# STM32L476VE.net
KiCad netlist of a schematic drawn in Altium Designer
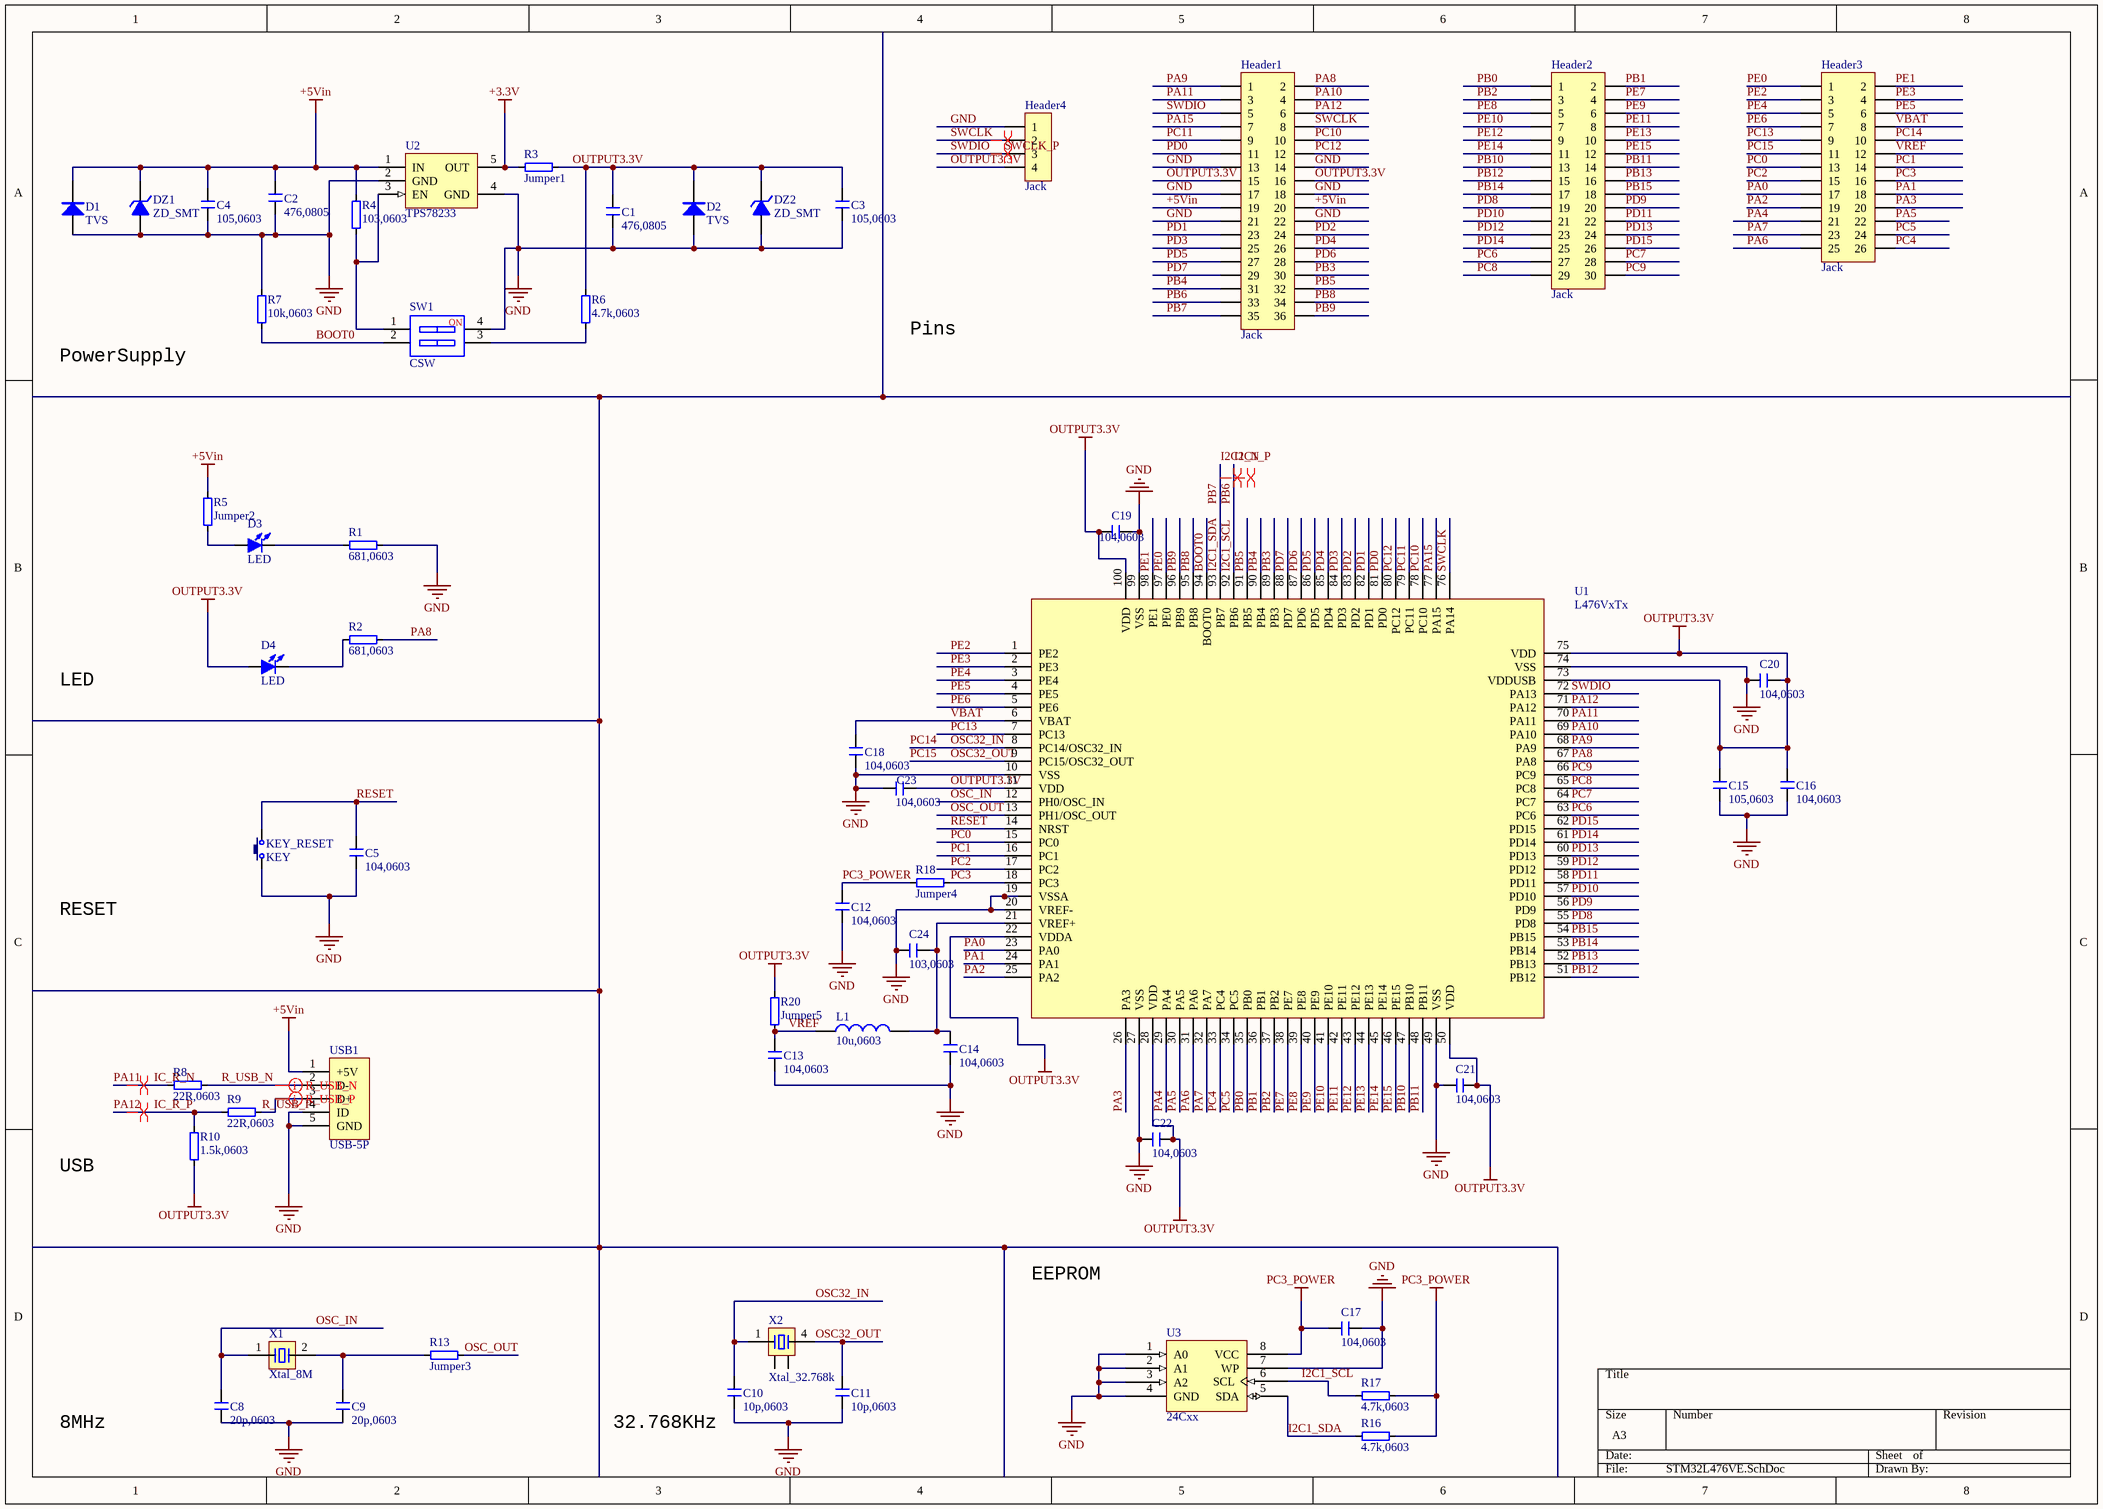
[diagram p0: STM32L476VE.SchDoc]

(export (version "E")
  (design (tool "Eeschema 10.0.6"))
  (components
    (comp (ref "C1")
      (value "476,0805")
      (footprint "0805C")
      (description "SMT0805")
      (libsource (lib "STM32L476VE") (part "CC_SMT_1"))
    )
    (comp (ref "C2")
      (value "476,0805")
      (footprint "0805C")
      (description "SMT0805")
      (libsource (lib "STM32L476VE") (part "CC_SMT_1"))
    )
    (comp (ref "C3")
      (value "105,0603")
      (footprint "0603_R")
      (description "SMT0603")
      (libsource (lib "STM32L476VE") (part "CC_SMT"))
    )
    (comp (ref "C4")
      (value "105,0603")
      (footprint "0603_R")
      (description "SMT0603")
      (libsource (lib "STM32L476VE") (part "CC_SMT"))
    )
    (comp (ref "C5")
      (value "104,0603")
      (footprint "0603_R")
      (description "SMT0603")
      (libsource (lib "STM32L476VE") (part "CC_SMT"))
    )
    (comp (ref "C8")
      (value "20p,0603")
      (footprint "0603_R")
      (description "SMT0603")
      (libsource (lib "STM32L476VE") (part "CC_SMT"))
    )
    (comp (ref "C9")
      (value "20p,0603")
      (footprint "0603_R")
      (description "SMT0603")
      (libsource (lib "STM32L476VE") (part "CC_SMT"))
    )
    (comp (ref "C10")
      (value "10p,0603")
      (footprint "0603_R")
      (description "SMT0603")
      (libsource (lib "STM32L476VE") (part "CC_SMT"))
    )
    (comp (ref "C11")
      (value "10p,0603")
      (footprint "0603_R")
      (description "SMT0603")
      (libsource (lib "STM32L476VE") (part "CC_SMT"))
    )
    (comp (ref "C12")
      (value "104,0603")
      (footprint "0603_R")
      (description "SMT0603")
      (libsource (lib "STM32L476VE") (part "CC_SMT"))
    )
    (comp (ref "C13")
      (value "104,0603")
      (footprint "0603_R")
      (description "SMT0603")
      (libsource (lib "STM32L476VE") (part "CC_SMT"))
    )
    (comp (ref "C14")
      (value "104,0603")
      (footprint "0603_R")
      (description "SMT0603")
      (libsource (lib "STM32L476VE") (part "CC_SMT"))
    )
    (comp (ref "C15")
      (value "105,0603")
      (footprint "0603_R")
      (description "SMT0603")
      (libsource (lib "STM32L476VE") (part "CC_SMT"))
    )
    (comp (ref "C16")
      (value "104,0603")
      (footprint "0603_R")
      (description "SMT0603")
      (libsource (lib "STM32L476VE") (part "CC_SMT"))
    )
    (comp (ref "C17")
      (value "104,0603")
      (footprint "0603_R")
      (description "SMT0603")
      (libsource (lib "STM32L476VE") (part "CC_SMT"))
    )
    (comp (ref "C18")
      (value "104,0603")
      (footprint "0603_R")
      (description "SMT0603")
      (libsource (lib "STM32L476VE") (part "CC_SMT"))
    )
    (comp (ref "C19")
      (value "104,0603")
      (footprint "0603_R")
      (description "SMT0603")
      (libsource (lib "STM32L476VE") (part "CC_SMT"))
    )
    (comp (ref "C20")
      (value "104,0603")
      (footprint "0603_R")
      (description "SMT0603")
      (libsource (lib "STM32L476VE") (part "CC_SMT"))
    )
    (comp (ref "C21")
      (value "104,0603")
      (footprint "0603_R")
      (description "SMT0603")
      (libsource (lib "STM32L476VE") (part "CC_SMT"))
    )
    (comp (ref "C22")
      (value "104,0603")
      (footprint "0603_R")
      (description "SMT0603")
      (libsource (lib "STM32L476VE") (part "CC_SMT"))
    )
    (comp (ref "C23")
      (value "104,0603")
      (footprint "0603_R")
      (description "SMT0603")
      (libsource (lib "STM32L476VE") (part "CC_SMT"))
    )
    (comp (ref "C24")
      (value "103,0603")
      (footprint "0603_R")
      (description "SMT0603")
      (libsource (lib "STM32L476VE") (part "CC_SMT"))
    )
    (comp (ref "D1")
      (value "TVS")
      (footprint "SMB(DO-214AA)_S3")
      (description "TVS Diode")
      (fields (field (name "版权归属") "源创客"))
      (libsource (lib "STM32L476VE") (part "TVS_SMT"))
    )
    (comp (ref "D2")
      (value "TVS")
      (footprint "SMB(DO-214AA)_S3")
      (description "TVS Diode")
      (fields (field (name "版权归属") "源创客"))
      (libsource (lib "STM32L476VE") (part "TVS_SMT"))
    )
    (comp (ref "D3")
      (value "LED")
      (footprint "LED0603")
      (description "LED_0603")
      (libsource (lib "STM32L476VE") (part "LED0603"))
    )
    (comp (ref "D4")
      (value "LED")
      (footprint "LED0603")
      (description "LED_0603")
      (libsource (lib "STM32L476VE") (part "LED0603"))
    )
    (comp (ref "DZ1")
      (value "ZD_SMT")
      (footprint "MINI_MELF (LL34)")
      (description "Zener")
      (libsource (lib "STM32L476VE") (part "ZD_SMT"))
    )
    (comp (ref "DZ2")
      (value "ZD_SMT")
      (footprint "MINI_MELF (LL34)")
      (description "Zener")
      (libsource (lib "STM32L476VE") (part "ZD_SMT"))
    )
    (comp (ref "Header1")
      (value "Jack")
      (footprint "HDR2.54-LI-2x18P")
      (description "Header Male")
      (libsource (lib "STM32L476VE") (part "M_18X2Pins_2.54-DIP"))
    )
    (comp (ref "Header2")
      (value "Jack")
      (footprint "HDR2.54-LI-2x15P")
      (description "Header Male")
      (libsource (lib "STM32L476VE") (part "M_15X2Pins_2.54-DIP"))
    )
    (comp (ref "Header3")
      (value "Jack")
      (footprint "HDR2.54-LI-2x13P")
      (description "Header Male")
      (libsource (lib "STM32L476VE") (part "M_13X2Pins_2.54-DIP"))
    )
    (comp (ref "Header4")
      (value "Jack")
      (footprint "HDR2.54-LI-4P")
      (description "Header Male")
      (libsource (lib "STM32L476VE") (part "M_4Pins_2.54-DIP"))
    )
    (comp (ref "KEY_RESET")
      (value "KEY")
      (footprint "TSW SMD-4*4*1.5")
      (description "Tact Switch")
      (libsource (lib "STM32L476VE") (part "TSW_4x4-SMT"))
    )
    (comp (ref "L1")
      (value "10u,0603")
      (footprint "L 0603")
      (description "SMT_0603")
      (libsource (lib "STM32L476VE") (part "L_SMT"))
    )
    (comp (ref "R1")
      (value "681,0603")
      (footprint "0603_R")
      (description "SMT_0603")
      (libsource (lib "STM32L476VE") (part "R_SMT"))
    )
    (comp (ref "R2")
      (value "681,0603")
      (footprint "0603_R")
      (description "SMT_0603")
      (libsource (lib "STM32L476VE") (part "R_SMT"))
    )
    (comp (ref "R3")
      (value "Jumper1")
      (footprint "0805C")
      (description "SMT_0805")
      (libsource (lib "STM32L476VE") (part "R_SMT_1"))
    )
    (comp (ref "R4")
      (value "103,0603")
      (footprint "0603_R")
      (description "SMT_0603")
      (libsource (lib "STM32L476VE") (part "R_SMT"))
    )
    (comp (ref "R5")
      (value "Jumper2")
      (footprint "0603_R")
      (description "SMT_0603")
      (libsource (lib "STM32L476VE") (part "R_SMT"))
    )
    (comp (ref "R6")
      (value "4.7k,0603")
      (footprint "0603_R")
      (description "SMT_0603")
      (libsource (lib "STM32L476VE") (part "R_SMT"))
    )
    (comp (ref "R7")
      (value "10k,0603")
      (footprint "0603_R")
      (description "SMT_0603")
      (libsource (lib "STM32L476VE") (part "R_SMT"))
    )
    (comp (ref "R8")
      (value "22R,0603")
      (footprint "0603_R")
      (description "SMT_0603")
      (libsource (lib "STM32L476VE") (part "R_SMT"))
    )
    (comp (ref "R9")
      (value "22R,0603")
      (footprint "0603_R")
      (description "SMT_0603")
      (libsource (lib "STM32L476VE") (part "R_SMT"))
    )
    (comp (ref "R10")
      (value "1.5k,0603")
      (footprint "0603_R")
      (description "SMT_0603")
      (libsource (lib "STM32L476VE") (part "R_SMT"))
    )
    (comp (ref "R13")
      (value "Jumper3")
      (footprint "0603_R")
      (description "SMT_0603")
      (libsource (lib "STM32L476VE") (part "R_SMT"))
    )
    (comp (ref "R16")
      (value "4.7k,0603")
      (footprint "0603_R")
      (description "SMT_0603")
      (libsource (lib "STM32L476VE") (part "R_SMT"))
    )
    (comp (ref "R17")
      (value "4.7k,0603")
      (footprint "0603_R")
      (description "SMT_0603")
      (libsource (lib "STM32L476VE") (part "R_SMT"))
    )
    (comp (ref "R18")
      (value "Jumper4")
      (footprint "0603_R")
      (description "SMT_0603")
      (libsource (lib "STM32L476VE") (part "R_SMT"))
    )
    (comp (ref "R20")
      (value "Jumper5")
      (footprint "0603_R")
      (description "SMT_0603")
      (libsource (lib "STM32L476VE") (part "R_SMT"))
    )
    (comp (ref "SW1")
      (value "CSW")
      (footprint "CSW1.27 SMD-2P")
      (description "DialSwitch")
      (libsource (lib "STM32L476VE") (part "Switch2_SMT"))
    )
    (comp (ref "U1")
      (value "L476VxTx")
      (footprint "LQFP-100_14x14x05P")
      (libsource (lib "STM32L476VE") (part "STM32L476VxTx"))
    )
    (comp (ref "U2")
      (value "TPS78233")
      (footprint "SOT23-5L")
      (description "Regulator_SMT")
      (fields (field (name "版权归属") "源创客"))
      (libsource (lib "STM32L476VE") (part "TPS782"))
    )
    (comp (ref "U3")
      (value "24Cxx")
      (footprint "SOIC-8_150mil")
      (description "外置EEPROM")
      (fields (field (name "版权归属") "源创客"))
      (libsource (lib "STM32L476VE") (part "24Cxx"))
    )
    (comp (ref "USB1")
      (value "USB-5P")
      (footprint "USB-MICRO_E")
      (description "USB_SMT")
      (fields (field (name "版权归属") "源创客"))
      (libsource (lib "STM32L476VE") (part "USB-5P"))
    )
    (comp (ref "X1")
      (value "Xtal_8M")
      (footprint "SMD-5032_2P")
      (fields (field (name "版权归属") "源创客"))
      (libsource (lib "STM32L476VE") (part "XTAL_8M_SMT"))
    )
    (comp (ref "X2")
      (value "Xtal_32.768k")
      (footprint "OSC MC-306")
      (fields (field (name "版权归属") "源创客"))
      (libsource (lib "STM32L476VE") (part "XTAL_32.768K_SMT"))
    )
  )
  (nets
    (net (code "1") (name "+3.3V") (class "Default")
      (node (ref "R3") (pin "1") (pinfunction "1_1") (pintype "passive"))
      (node (ref "U2") (pin "5") (pinfunction "OUT_5") (pintype "passive"))
    )
    (net (code "2") (name "+5Vin") (class "Default")
      (node (ref "C2") (pin "1") (pinfunction "1_1") (pintype "passive"))
      (node (ref "C4") (pin "1") (pinfunction "1_1") (pintype "passive"))
      (node (ref "D1") (pin "2") (pinfunction "K_2") (pintype "passive"))
      (node (ref "DZ1") (pin "2") (pinfunction "K_2") (pintype "passive"))
      (node (ref "Header1") (pin "19") (pinfunction "19_19") (pintype "passive"))
      (node (ref "Header1") (pin "20") (pinfunction "20_20") (pintype "passive"))
      (node (ref "R4") (pin "2") (pinfunction "2_2") (pintype "passive"))
      (node (ref "R5") (pin "2") (pinfunction "2_2") (pintype "passive"))
      (node (ref "U2") (pin "1") (pinfunction "IN_1") (pintype "passive"))
      (node (ref "USB1") (pin "1") (pinfunction "+5V_1") (pintype "passive"))
    )
    (net (code "3") (name "/BOOT0") (class "Default")
      (node (ref "R7") (pin "2") (pinfunction "2_2") (pintype "passive"))
      (node (ref "SW1") (pin "2") (pinfunction "2_2") (pintype "passive"))
      (node (ref "U1") (pin "94") (pinfunction "BOOT0_94") (pintype "passive"))
    )
    (net (code "4") (name "/I2C1_N") (class "Default")
      (node (ref "Header1") (pin "35") (pinfunction "35_35") (pintype "passive"))
      (node (ref "R16") (pin "1") (pinfunction "1_1") (pintype "passive"))
      (node (ref "U1") (pin "93") (pinfunction "PB7_93") (pintype "passive"))
      (node (ref "U3") (pin "5") (pinfunction "SDA_5") (pintype "bidirectional"))
    )
    (net (code "5") (name "/I2C1_P") (class "Default")
      (node (ref "Header1") (pin "33") (pinfunction "33_33") (pintype "passive"))
      (node (ref "R17") (pin "1") (pinfunction "1_1") (pintype "passive"))
      (node (ref "U1") (pin "92") (pinfunction "PB6_92") (pintype "passive"))
      (node (ref "U3") (pin "6") (pinfunction "SCL_6") (pintype "input"))
    )
    (net (code "6") (name "/IC_R_N") (class "Default")
      (node (ref "Header1") (pin "3") (pinfunction "3_3") (pintype "passive"))
      (node (ref "R8") (pin "1") (pinfunction "1_1") (pintype "passive"))
      (node (ref "U1") (pin "70") (pinfunction "PA11_70") (pintype "passive"))
    )
    (net (code "7") (name "/IC_R_P") (class "Default")
      (node (ref "Header1") (pin "6") (pinfunction "6_6") (pintype "passive"))
      (node (ref "R10") (pin "2") (pinfunction "2_2") (pintype "passive"))
      (node (ref "R9") (pin "1") (pinfunction "1_1") (pintype "passive"))
      (node (ref "U1") (pin "71") (pinfunction "PA12_71") (pintype "passive"))
    )
    (net (code "8") (name "/OSC32_IN") (class "Default")
      (node (ref "C10") (pin "1") (pinfunction "1_1") (pintype "passive"))
      (node (ref "Header3") (pin "10") (pinfunction "10_10") (pintype "passive"))
      (node (ref "U1") (pin "8") (pinfunction "PC14/OSC32_IN_8") (pintype "passive"))
      (node (ref "X2") (pin "1") (pinfunction "1_1") (pintype "passive"))
    )
    (net (code "9") (name "/OSC32_OUT") (class "Default")
      (node (ref "C11") (pin "1") (pinfunction "1_1") (pintype "passive"))
      (node (ref "Header3") (pin "11") (pinfunction "11_11") (pintype "passive"))
      (node (ref "U1") (pin "9") (pinfunction "PC15/OSC32_OUT_9") (pintype "passive"))
      (node (ref "X2") (pin "4") (pinfunction "4_4") (pintype "passive"))
    )
    (net (code "10") (name "/OSC_IN") (class "Default")
      (node (ref "C8") (pin "1") (pinfunction "1_1") (pintype "passive"))
      (node (ref "U1") (pin "12") (pinfunction "PH0/OSC_IN_12") (pintype "passive"))
      (node (ref "X1") (pin "1") (pinfunction "1_1") (pintype "passive"))
    )
    (net (code "11") (name "/OSC_OUT") (class "Default")
      (node (ref "R13") (pin "2") (pinfunction "2_2") (pintype "passive"))
      (node (ref "U1") (pin "13") (pinfunction "PH1/OSC_OUT_13") (pintype "passive"))
    )
    (net (code "12") (name "/PA0") (class "Default")
      (node (ref "Header3") (pin "17") (pinfunction "17_17") (pintype "passive"))
      (node (ref "U1") (pin "23") (pinfunction "PA0_23") (pintype "passive"))
    )
    (net (code "13") (name "/PA1") (class "Default")
      (node (ref "Header3") (pin "18") (pinfunction "18_18") (pintype "passive"))
      (node (ref "U1") (pin "24") (pinfunction "PA1_24") (pintype "passive"))
    )
    (net (code "14") (name "/PA2") (class "Default")
      (node (ref "Header3") (pin "19") (pinfunction "19_19") (pintype "passive"))
      (node (ref "U1") (pin "25") (pinfunction "PA2_25") (pintype "passive"))
    )
    (net (code "15") (name "/PA3") (class "Default")
      (node (ref "Header3") (pin "20") (pinfunction "20_20") (pintype "passive"))
      (node (ref "U1") (pin "26") (pinfunction "PA3_26") (pintype "passive"))
    )
    (net (code "16") (name "/PA4") (class "Default")
      (node (ref "Header3") (pin "21") (pinfunction "21_21") (pintype "passive"))
      (node (ref "U1") (pin "29") (pinfunction "PA4_29") (pintype "passive"))
    )
    (net (code "17") (name "/PA5") (class "Default")
      (node (ref "Header3") (pin "22") (pinfunction "22_22") (pintype "passive"))
      (node (ref "U1") (pin "30") (pinfunction "PA5_30") (pintype "passive"))
    )
    (net (code "18") (name "/PA6") (class "Default")
      (node (ref "Header3") (pin "25") (pinfunction "25_25") (pintype "passive"))
      (node (ref "U1") (pin "31") (pinfunction "PA6_31") (pintype "passive"))
    )
    (net (code "19") (name "/PA7") (class "Default")
      (node (ref "Header3") (pin "23") (pinfunction "23_23") (pintype "passive"))
      (node (ref "U1") (pin "32") (pinfunction "PA7_32") (pintype "passive"))
    )
    (net (code "20") (name "/PA8") (class "Default")
      (node (ref "Header1") (pin "2") (pinfunction "2_2") (pintype "passive"))
      (node (ref "R2") (pin "2") (pinfunction "2_2") (pintype "passive"))
      (node (ref "U1") (pin "67") (pinfunction "PA8_67") (pintype "passive"))
    )
    (net (code "21") (name "/PA9") (class "Default")
      (node (ref "Header1") (pin "1") (pinfunction "1_1") (pintype "passive"))
      (node (ref "U1") (pin "68") (pinfunction "PA9_68") (pintype "passive"))
    )
    (net (code "22") (name "/PA10") (class "Default")
      (node (ref "Header1") (pin "4") (pinfunction "4_4") (pintype "passive"))
      (node (ref "U1") (pin "69") (pinfunction "PA10_69") (pintype "passive"))
    )
    (net (code "23") (name "/PA15") (class "Default")
      (node (ref "Header1") (pin "7") (pinfunction "7_7") (pintype "passive"))
      (node (ref "U1") (pin "77") (pinfunction "PA15_77") (pintype "passive"))
    )
    (net (code "24") (name "/PB0") (class "Default")
      (node (ref "Header2") (pin "1") (pinfunction "1_1") (pintype "passive"))
      (node (ref "U1") (pin "35") (pinfunction "PB0_35") (pintype "passive"))
    )
    (net (code "25") (name "/PB1") (class "Default")
      (node (ref "Header2") (pin "2") (pinfunction "2_2") (pintype "passive"))
      (node (ref "U1") (pin "36") (pinfunction "PB1_36") (pintype "passive"))
    )
    (net (code "26") (name "/PB2") (class "Default")
      (node (ref "Header2") (pin "3") (pinfunction "3_3") (pintype "passive"))
      (node (ref "U1") (pin "37") (pinfunction "PB2_37") (pintype "passive"))
    )
    (net (code "27") (name "/PB3") (class "Default")
      (node (ref "Header1") (pin "30") (pinfunction "30_30") (pintype "passive"))
      (node (ref "U1") (pin "89") (pinfunction "PB3_89") (pintype "passive"))
    )
    (net (code "28") (name "/PB4") (class "Default")
      (node (ref "Header1") (pin "31") (pinfunction "31_31") (pintype "passive"))
      (node (ref "U1") (pin "90") (pinfunction "PB4_90") (pintype "passive"))
    )
    (net (code "29") (name "/PB5") (class "Default")
      (node (ref "Header1") (pin "32") (pinfunction "32_32") (pintype "passive"))
      (node (ref "U1") (pin "91") (pinfunction "PB5_91") (pintype "passive"))
    )
    (net (code "30") (name "/PB8") (class "Default")
      (node (ref "Header1") (pin "34") (pinfunction "34_34") (pintype "passive"))
      (node (ref "U1") (pin "95") (pinfunction "PB8_95") (pintype "passive"))
    )
    (net (code "31") (name "/PB9") (class "Default")
      (node (ref "Header1") (pin "36") (pinfunction "36_36") (pintype "passive"))
      (node (ref "U1") (pin "96") (pinfunction "PB9_96") (pintype "passive"))
    )
    (net (code "32") (name "/PB10") (class "Default")
      (node (ref "Header2") (pin "13") (pinfunction "13_13") (pintype "passive"))
      (node (ref "U1") (pin "47") (pinfunction "PB10_47") (pintype "passive"))
    )
    (net (code "33") (name "/PB11") (class "Default")
      (node (ref "Header2") (pin "14") (pinfunction "14_14") (pintype "passive"))
      (node (ref "U1") (pin "48") (pinfunction "PB11_48") (pintype "passive"))
    )
    (net (code "34") (name "/PB12") (class "Default")
      (node (ref "Header2") (pin "15") (pinfunction "15_15") (pintype "passive"))
      (node (ref "U1") (pin "51") (pinfunction "PB12_51") (pintype "passive"))
    )
    (net (code "35") (name "/PB13") (class "Default")
      (node (ref "Header2") (pin "16") (pinfunction "16_16") (pintype "passive"))
      (node (ref "U1") (pin "52") (pinfunction "PB13_52") (pintype "passive"))
    )
    (net (code "36") (name "/PB14") (class "Default")
      (node (ref "Header2") (pin "17") (pinfunction "17_17") (pintype "passive"))
      (node (ref "U1") (pin "53") (pinfunction "PB14_53") (pintype "passive"))
    )
    (net (code "37") (name "/PB15") (class "Default")
      (node (ref "Header2") (pin "18") (pinfunction "18_18") (pintype "passive"))
      (node (ref "U1") (pin "54") (pinfunction "PB15_54") (pintype "passive"))
    )
    (net (code "38") (name "/PC0") (class "Default")
      (node (ref "Header3") (pin "13") (pinfunction "13_13") (pintype "passive"))
      (node (ref "U1") (pin "15") (pinfunction "PC0_15") (pintype "passive"))
    )
    (net (code "39") (name "/PC1") (class "Default")
      (node (ref "Header3") (pin "14") (pinfunction "14_14") (pintype "passive"))
      (node (ref "U1") (pin "16") (pinfunction "PC1_16") (pintype "passive"))
    )
    (net (code "40") (name "/PC2") (class "Default")
      (node (ref "Header3") (pin "15") (pinfunction "15_15") (pintype "passive"))
      (node (ref "U1") (pin "17") (pinfunction "PC2_17") (pintype "passive"))
    )
    (net (code "41") (name "/PC3") (class "Default")
      (node (ref "Header3") (pin "16") (pinfunction "16_16") (pintype "passive"))
      (node (ref "R18") (pin "2") (pinfunction "2_2") (pintype "passive"))
      (node (ref "U1") (pin "18") (pinfunction "PC3_18") (pintype "passive"))
    )
    (net (code "42") (name "/PC4") (class "Default")
      (node (ref "Header3") (pin "26") (pinfunction "26_26") (pintype "passive"))
      (node (ref "U1") (pin "33") (pinfunction "PC4_33") (pintype "passive"))
    )
    (net (code "43") (name "/PC5") (class "Default")
      (node (ref "Header3") (pin "24") (pinfunction "24_24") (pintype "passive"))
      (node (ref "U1") (pin "34") (pinfunction "PC5_34") (pintype "passive"))
    )
    (net (code "44") (name "/PC6") (class "Default")
      (node (ref "Header2") (pin "27") (pinfunction "27_27") (pintype "passive"))
      (node (ref "U1") (pin "63") (pinfunction "PC6_63") (pintype "passive"))
    )
    (net (code "45") (name "/PC7") (class "Default")
      (node (ref "Header2") (pin "28") (pinfunction "28_28") (pintype "passive"))
      (node (ref "U1") (pin "64") (pinfunction "PC7_64") (pintype "passive"))
    )
    (net (code "46") (name "/PC8") (class "Default")
      (node (ref "Header2") (pin "29") (pinfunction "29_29") (pintype "passive"))
      (node (ref "U1") (pin "65") (pinfunction "PC8_65") (pintype "passive"))
    )
    (net (code "47") (name "/PC9") (class "Default")
      (node (ref "Header2") (pin "30") (pinfunction "30_30") (pintype "passive"))
      (node (ref "U1") (pin "66") (pinfunction "PC9_66") (pintype "passive"))
    )
    (net (code "48") (name "/PC10") (class "Default")
      (node (ref "Header1") (pin "10") (pinfunction "10_10") (pintype "passive"))
      (node (ref "U1") (pin "78") (pinfunction "PC10_78") (pintype "passive"))
    )
    (net (code "49") (name "/PC11") (class "Default")
      (node (ref "Header1") (pin "9") (pinfunction "9_9") (pintype "passive"))
      (node (ref "U1") (pin "79") (pinfunction "PC11_79") (pintype "passive"))
    )
    (net (code "50") (name "/PC12") (class "Default")
      (node (ref "Header1") (pin "12") (pinfunction "12_12") (pintype "passive"))
      (node (ref "U1") (pin "80") (pinfunction "PC12_80") (pintype "passive"))
    )
    (net (code "51") (name "/PC13") (class "Default")
      (node (ref "Header3") (pin "9") (pinfunction "9_9") (pintype "passive"))
      (node (ref "U1") (pin "7") (pinfunction "PC13_7") (pintype "passive"))
    )
    (net (code "52") (name "/PD0") (class "Default")
      (node (ref "Header1") (pin "11") (pinfunction "11_11") (pintype "passive"))
      (node (ref "U1") (pin "81") (pinfunction "PD0_81") (pintype "passive"))
    )
    (net (code "53") (name "/PD1") (class "Default")
      (node (ref "Header1") (pin "23") (pinfunction "23_23") (pintype "passive"))
      (node (ref "U1") (pin "82") (pinfunction "PD1_82") (pintype "passive"))
    )
    (net (code "54") (name "/PD2") (class "Default")
      (node (ref "Header1") (pin "24") (pinfunction "24_24") (pintype "passive"))
      (node (ref "U1") (pin "83") (pinfunction "PD2_83") (pintype "passive"))
    )
    (net (code "55") (name "/PD3") (class "Default")
      (node (ref "Header1") (pin "25") (pinfunction "25_25") (pintype "passive"))
      (node (ref "U1") (pin "84") (pinfunction "PD3_84") (pintype "passive"))
    )
    (net (code "56") (name "/PD4") (class "Default")
      (node (ref "Header1") (pin "26") (pinfunction "26_26") (pintype "passive"))
      (node (ref "U1") (pin "85") (pinfunction "PD4_85") (pintype "passive"))
    )
    (net (code "57") (name "/PD5") (class "Default")
      (node (ref "Header1") (pin "27") (pinfunction "27_27") (pintype "passive"))
      (node (ref "U1") (pin "86") (pinfunction "PD5_86") (pintype "passive"))
    )
    (net (code "58") (name "/PD6") (class "Default")
      (node (ref "Header1") (pin "28") (pinfunction "28_28") (pintype "passive"))
      (node (ref "U1") (pin "87") (pinfunction "PD6_87") (pintype "passive"))
    )
    (net (code "59") (name "/PD7") (class "Default")
      (node (ref "Header1") (pin "29") (pinfunction "29_29") (pintype "passive"))
      (node (ref "U1") (pin "88") (pinfunction "PD7_88") (pintype "passive"))
    )
    (net (code "60") (name "/PD8") (class "Default")
      (node (ref "Header2") (pin "19") (pinfunction "19_19") (pintype "passive"))
      (node (ref "U1") (pin "55") (pinfunction "PD8_55") (pintype "passive"))
    )
    (net (code "61") (name "/PD9") (class "Default")
      (node (ref "Header2") (pin "20") (pinfunction "20_20") (pintype "passive"))
      (node (ref "U1") (pin "56") (pinfunction "PD9_56") (pintype "passive"))
    )
    (net (code "62") (name "/PD10") (class "Default")
      (node (ref "Header2") (pin "21") (pinfunction "21_21") (pintype "passive"))
      (node (ref "U1") (pin "57") (pinfunction "PD10_57") (pintype "passive"))
    )
    (net (code "63") (name "/PD11") (class "Default")
      (node (ref "Header2") (pin "22") (pinfunction "22_22") (pintype "passive"))
      (node (ref "U1") (pin "58") (pinfunction "PD11_58") (pintype "passive"))
    )
    (net (code "64") (name "/PD12") (class "Default")
      (node (ref "Header2") (pin "23") (pinfunction "23_23") (pintype "passive"))
      (node (ref "U1") (pin "59") (pinfunction "PD12_59") (pintype "passive"))
    )
    (net (code "65") (name "/PD13") (class "Default")
      (node (ref "Header2") (pin "24") (pinfunction "24_24") (pintype "passive"))
      (node (ref "U1") (pin "60") (pinfunction "PD13_60") (pintype "passive"))
    )
    (net (code "66") (name "/PD14") (class "Default")
      (node (ref "Header2") (pin "25") (pinfunction "25_25") (pintype "passive"))
      (node (ref "U1") (pin "61") (pinfunction "PD14_61") (pintype "passive"))
    )
    (net (code "67") (name "/PD15") (class "Default")
      (node (ref "Header2") (pin "26") (pinfunction "26_26") (pintype "passive"))
      (node (ref "U1") (pin "62") (pinfunction "PD15_62") (pintype "passive"))
    )
    (net (code "68") (name "/PE0") (class "Default")
      (node (ref "Header3") (pin "1") (pinfunction "1_1") (pintype "passive"))
      (node (ref "U1") (pin "97") (pinfunction "PE0_97") (pintype "passive"))
    )
    (net (code "69") (name "/PE1") (class "Default")
      (node (ref "Header3") (pin "2") (pinfunction "2_2") (pintype "passive"))
      (node (ref "U1") (pin "98") (pinfunction "PE1_98") (pintype "passive"))
    )
    (net (code "70") (name "/PE2") (class "Default")
      (node (ref "Header3") (pin "3") (pinfunction "3_3") (pintype "passive"))
      (node (ref "U1") (pin "1") (pinfunction "PE2_1") (pintype "passive"))
    )
    (net (code "71") (name "/PE3") (class "Default")
      (node (ref "Header3") (pin "4") (pinfunction "4_4") (pintype "passive"))
      (node (ref "U1") (pin "2") (pinfunction "PE3_2") (pintype "passive"))
    )
    (net (code "72") (name "/PE4") (class "Default")
      (node (ref "Header3") (pin "5") (pinfunction "5_5") (pintype "passive"))
      (node (ref "U1") (pin "3") (pinfunction "PE4_3") (pintype "passive"))
    )
    (net (code "73") (name "/PE5") (class "Default")
      (node (ref "Header3") (pin "6") (pinfunction "6_6") (pintype "passive"))
      (node (ref "U1") (pin "4") (pinfunction "PE5_4") (pintype "passive"))
    )
    (net (code "74") (name "/PE6") (class "Default")
      (node (ref "Header3") (pin "7") (pinfunction "7_7") (pintype "passive"))
      (node (ref "U1") (pin "5") (pinfunction "PE6_5") (pintype "passive"))
    )
    (net (code "75") (name "/PE7") (class "Default")
      (node (ref "Header2") (pin "4") (pinfunction "4_4") (pintype "passive"))
      (node (ref "U1") (pin "38") (pinfunction "PE7_38") (pintype "passive"))
    )
    (net (code "76") (name "/PE8") (class "Default")
      (node (ref "Header2") (pin "5") (pinfunction "5_5") (pintype "passive"))
      (node (ref "U1") (pin "39") (pinfunction "PE8_39") (pintype "passive"))
    )
    (net (code "77") (name "/PE9") (class "Default")
      (node (ref "Header2") (pin "6") (pinfunction "6_6") (pintype "passive"))
      (node (ref "U1") (pin "40") (pinfunction "PE9_40") (pintype "passive"))
    )
    (net (code "78") (name "/PE10") (class "Default")
      (node (ref "Header2") (pin "7") (pinfunction "7_7") (pintype "passive"))
      (node (ref "U1") (pin "41") (pinfunction "PE10_41") (pintype "passive"))
    )
    (net (code "79") (name "/PE11") (class "Default")
      (node (ref "Header2") (pin "8") (pinfunction "8_8") (pintype "passive"))
      (node (ref "U1") (pin "42") (pinfunction "PE11_42") (pintype "passive"))
    )
    (net (code "80") (name "/PE12") (class "Default")
      (node (ref "Header2") (pin "9") (pinfunction "9_9") (pintype "passive"))
      (node (ref "U1") (pin "43") (pinfunction "PE12_43") (pintype "passive"))
    )
    (net (code "81") (name "/PE13") (class "Default")
      (node (ref "Header2") (pin "10") (pinfunction "10_10") (pintype "passive"))
      (node (ref "U1") (pin "44") (pinfunction "PE13_44") (pintype "passive"))
    )
    (net (code "82") (name "/PE14") (class "Default")
      (node (ref "Header2") (pin "11") (pinfunction "11_11") (pintype "passive"))
      (node (ref "U1") (pin "45") (pinfunction "PE14_45") (pintype "passive"))
    )
    (net (code "83") (name "/PE15") (class "Default")
      (node (ref "Header2") (pin "12") (pinfunction "12_12") (pintype "passive"))
      (node (ref "U1") (pin "46") (pinfunction "PE15_46") (pintype "passive"))
    )
    (net (code "84") (name "/RESET") (class "Default")
      (node (ref "C5") (pin "1") (pinfunction "1_1") (pintype "passive"))
      (node (ref "KEY_RESET") (pin "2") (pinfunction "2_2") (pintype "passive"))
      (node (ref "U1") (pin "14") (pinfunction "NRST_14") (pintype "passive"))
    )
    (net (code "85") (name "/R_USB_N") (class "Default")
      (node (ref "R8") (pin "2") (pinfunction "2_2") (pintype "passive"))
      (node (ref "USB1") (pin "2") (pinfunction "D-_2") (pintype "passive"))
    )
    (net (code "86") (name "/R_USB_P") (class "Default")
      (node (ref "R9") (pin "2") (pinfunction "2_2") (pintype "passive"))
      (node (ref "USB1") (pin "3") (pinfunction "D+_3") (pintype "passive"))
    )
    (net (code "87") (name "/SWCLK") (class "Default")
      (node (ref "Header1") (pin "8") (pinfunction "8_8") (pintype "passive"))
      (node (ref "Header4") (pin "2") (pinfunction "2_2") (pintype "passive"))
      (node (ref "U1") (pin "76") (pinfunction "PA14_76") (pintype "passive"))
    )
    (net (code "88") (name "/SWCLK_P") (class "Default")
      (node (ref "Header1") (pin "5") (pinfunction "5_5") (pintype "passive"))
      (node (ref "Header4") (pin "3") (pinfunction "3_3") (pintype "passive"))
      (node (ref "U1") (pin "72") (pinfunction "PA13_72") (pintype "passive"))
    )
    (net (code "89") (name "/VBAT") (class "Default")
      (node (ref "C18") (pin "1") (pinfunction "1_1") (pintype "passive"))
      (node (ref "Header3") (pin "8") (pinfunction "8_8") (pintype "passive"))
      (node (ref "U1") (pin "6") (pinfunction "VBAT_6") (pintype "passive"))
    )
    (net (code "90") (name "/VREF") (class "Default")
      (node (ref "C13") (pin "1") (pinfunction "1_1") (pintype "passive"))
      (node (ref "Header3") (pin "12") (pinfunction "12_12") (pintype "passive"))
      (node (ref "L1") (pin "1") (pinfunction "1_1") (pintype "passive"))
      (node (ref "R20") (pin "1") (pinfunction "1_1") (pintype "passive"))
    )
    (net (code "91") (name "GND") (class "Default")
      (node (ref "C1") (pin "2") (pinfunction "2_2") (pintype "passive"))
      (node (ref "C10") (pin "2") (pinfunction "2_2") (pintype "passive"))
      (node (ref "C11") (pin "2") (pinfunction "2_2") (pintype "passive"))
      (node (ref "C12") (pin "2") (pinfunction "2_2") (pintype "passive"))
      (node (ref "C13") (pin "2") (pinfunction "2_2") (pintype "passive"))
      (node (ref "C14") (pin "2") (pinfunction "2_2") (pintype "passive"))
      (node (ref "C15") (pin "2") (pinfunction "2_2") (pintype "passive"))
      (node (ref "C16") (pin "2") (pinfunction "2_2") (pintype "passive"))
      (node (ref "C17") (pin "2") (pinfunction "2_2") (pintype "passive"))
      (node (ref "C18") (pin "2") (pinfunction "2_2") (pintype "passive"))
      (node (ref "C19") (pin "2") (pinfunction "2_2") (pintype "passive"))
      (node (ref "C2") (pin "2") (pinfunction "2_2") (pintype "passive"))
      (node (ref "C20") (pin "1") (pinfunction "1_1") (pintype "passive"))
      (node (ref "C21") (pin "1") (pinfunction "1_1") (pintype "passive"))
      (node (ref "C22") (pin "1") (pinfunction "1_1") (pintype "passive"))
      (node (ref "C23") (pin "2") (pinfunction "2_2") (pintype "passive"))
      (node (ref "C24") (pin "1") (pinfunction "1_1") (pintype "passive"))
      (node (ref "C3") (pin "2") (pinfunction "2_2") (pintype "passive"))
      (node (ref "C4") (pin "2") (pinfunction "2_2") (pintype "passive"))
      (node (ref "C5") (pin "2") (pinfunction "2_2") (pintype "passive"))
      (node (ref "C8") (pin "2") (pinfunction "2_2") (pintype "passive"))
      (node (ref "C9") (pin "2") (pinfunction "2_2") (pintype "passive"))
      (node (ref "D1") (pin "1") (pinfunction "A_1") (pintype "passive"))
      (node (ref "D2") (pin "1") (pinfunction "A_1") (pintype "passive"))
      (node (ref "DZ1") (pin "1") (pinfunction "A_1") (pintype "passive"))
      (node (ref "DZ2") (pin "1") (pinfunction "A_1") (pintype "passive"))
      (node (ref "Header1") (pin "13") (pinfunction "13_13") (pintype "passive"))
      (node (ref "Header1") (pin "14") (pinfunction "14_14") (pintype "passive"))
      (node (ref "Header1") (pin "17") (pinfunction "17_17") (pintype "passive"))
      (node (ref "Header1") (pin "18") (pinfunction "18_18") (pintype "passive"))
      (node (ref "Header1") (pin "21") (pinfunction "21_21") (pintype "passive"))
      (node (ref "Header1") (pin "22") (pinfunction "22_22") (pintype "passive"))
      (node (ref "Header4") (pin "1") (pinfunction "1_1") (pintype "passive"))
      (node (ref "KEY_RESET") (pin "1") (pinfunction "1_1") (pintype "passive"))
      (node (ref "R1") (pin "2") (pinfunction "2_2") (pintype "passive"))
      (node (ref "R7") (pin "1") (pinfunction "1_1") (pintype "passive"))
      (node (ref "SW1") (pin "4") (pinfunction "4_4") (pintype "passive"))
      (node (ref "U1") (pin "10") (pinfunction "VSS_10") (pintype "passive"))
      (node (ref "U1") (pin "19") (pinfunction "VSSA_19") (pintype "passive"))
      (node (ref "U1") (pin "20") (pinfunction "VREF-_20") (pintype "passive"))
      (node (ref "U1") (pin "27") (pinfunction "VSS_27") (pintype "passive"))
      (node (ref "U1") (pin "49") (pinfunction "VSS_49") (pintype "passive"))
      (node (ref "U1") (pin "74") (pinfunction "VSS_74") (pintype "passive"))
      (node (ref "U1") (pin "99") (pinfunction "VSS_99") (pintype "passive"))
      (node (ref "U2") (pin "2") (pinfunction "GND_2") (pintype "passive"))
      (node (ref "U2") (pin "4") (pinfunction "GND_4") (pintype "passive"))
      (node (ref "U3") (pin "1") (pinfunction "A0_1") (pintype "input"))
      (node (ref "U3") (pin "2") (pinfunction "A1_2") (pintype "input"))
      (node (ref "U3") (pin "3") (pinfunction "A2_3") (pintype "input"))
      (node (ref "U3") (pin "4") (pinfunction "GND_4") (pintype "passive"))
      (node (ref "U3") (pin "7") (pinfunction "WP_7") (pintype "passive"))
      (node (ref "USB1") (pin "4") (pinfunction "ID_4") (pintype "passive"))
      (node (ref "USB1") (pin "5") (pinfunction "GND_5") (pintype "passive"))
    )
    (net (code "92") (name "Net-(C9-Pad1)") (class "Default")
      (node (ref "C9") (pin "1") (pinfunction "1_1") (pintype "passive"))
      (node (ref "R13") (pin "1") (pinfunction "1_1") (pintype "passive"))
      (node (ref "X1") (pin "2") (pinfunction "2_2") (pintype "passive"))
    )
    (net (code "93") (name "Net-(D3-A)") (class "Default")
      (node (ref "D3") (pin "1") (pinfunction "A_1") (pintype "passive"))
      (node (ref "R5") (pin "1") (pinfunction "1_1") (pintype "passive"))
    )
    (net (code "94") (name "Net-(D3-K)") (class "Default")
      (node (ref "D3") (pin "2") (pinfunction "K_2") (pintype "passive"))
      (node (ref "R1") (pin "1") (pinfunction "1_1") (pintype "passive"))
    )
    (net (code "95") (name "Net-(D4-K)") (class "Default")
      (node (ref "D4") (pin "2") (pinfunction "K_2") (pintype "passive"))
      (node (ref "R2") (pin "1") (pinfunction "1_1") (pintype "passive"))
    )
    (net (code "96") (name "Net-(R6-Pad1)") (class "Default")
      (node (ref "R6") (pin "1") (pinfunction "1_1") (pintype "passive"))
      (node (ref "SW1") (pin "3") (pinfunction "3_3") (pintype "passive"))
    )
    (net (code "97") (name "Net-(U1-VREF+)") (class "Default")
      (node (ref "C14") (pin "1") (pinfunction "1_1") (pintype "passive"))
      (node (ref "C24") (pin "2") (pinfunction "2_2") (pintype "passive"))
      (node (ref "L1") (pin "2") (pinfunction "2_2") (pintype "passive"))
      (node (ref "U1") (pin "21") (pinfunction "VREF+_21") (pintype "passive"))
    )
    (net (code "98") (name "Net-(U2-EN)") (class "Default")
      (node (ref "R4") (pin "1") (pinfunction "1_1") (pintype "passive"))
      (node (ref "SW1") (pin "1") (pinfunction "1_1") (pintype "passive"))
      (node (ref "U2") (pin "3") (pinfunction "EN_3") (pintype "input"))
    )
    (net (code "99") (name "OUTPUT3.3V") (class "Default")
      (node (ref "C1") (pin "1") (pinfunction "1_1") (pintype "passive"))
      (node (ref "C15") (pin "1") (pinfunction "1_1") (pintype "passive"))
      (node (ref "C16") (pin "1") (pinfunction "1_1") (pintype "passive"))
      (node (ref "C19") (pin "1") (pinfunction "1_1") (pintype "passive"))
      (node (ref "C20") (pin "2") (pinfunction "2_2") (pintype "passive"))
      (node (ref "C21") (pin "2") (pinfunction "2_2") (pintype "passive"))
      (node (ref "C22") (pin "2") (pinfunction "2_2") (pintype "passive"))
      (node (ref "C23") (pin "1") (pinfunction "1_1") (pintype "passive"))
      (node (ref "C3") (pin "1") (pinfunction "1_1") (pintype "passive"))
      (node (ref "D2") (pin "2") (pinfunction "K_2") (pintype "passive"))
      (node (ref "D4") (pin "1") (pinfunction "A_1") (pintype "passive"))
      (node (ref "DZ2") (pin "2") (pinfunction "K_2") (pintype "passive"))
      (node (ref "Header1") (pin "15") (pinfunction "15_15") (pintype "passive"))
      (node (ref "Header1") (pin "16") (pinfunction "16_16") (pintype "passive"))
      (node (ref "Header4") (pin "4") (pinfunction "4_4") (pintype "passive"))
      (node (ref "R10") (pin "1") (pinfunction "1_1") (pintype "passive"))
      (node (ref "R20") (pin "2") (pinfunction "2_2") (pintype "passive"))
      (node (ref "R3") (pin "2") (pinfunction "2_2") (pintype "passive"))
      (node (ref "R6") (pin "2") (pinfunction "2_2") (pintype "passive"))
      (node (ref "U1") (pin "100") (pinfunction "VDD_100") (pintype "passive"))
      (node (ref "U1") (pin "11") (pinfunction "VDD_11") (pintype "passive"))
      (node (ref "U1") (pin "22") (pinfunction "VDDA_22") (pintype "passive"))
      (node (ref "U1") (pin "28") (pinfunction "VDD_28") (pintype "passive"))
      (node (ref "U1") (pin "50") (pinfunction "VDD_50") (pintype "passive"))
      (node (ref "U1") (pin "73") (pinfunction "VDDUSB_73") (pintype "passive"))
      (node (ref "U1") (pin "75") (pinfunction "VDD_75") (pintype "passive"))
    )
    (net (code "100") (name "PC3_POWER") (class "Default")
      (node (ref "C12") (pin "1") (pinfunction "1_1") (pintype "passive"))
      (node (ref "C17") (pin "1") (pinfunction "1_1") (pintype "passive"))
      (node (ref "R16") (pin "2") (pinfunction "2_2") (pintype "passive"))
      (node (ref "R17") (pin "2") (pinfunction "2_2") (pintype "passive"))
      (node (ref "R18") (pin "1") (pinfunction "1_1") (pintype "passive"))
      (node (ref "U3") (pin "8") (pinfunction "VCC_8") (pintype "power_in"))
    )
    (net (code "101") (name "unconnected-(X2-Pad2)") (class "Default")
      (node (ref "X2") (pin "2") (pinfunction "2_2") (pintype "passive"))
    )
    (net (code "102") (name "unconnected-(X2-Pad3)") (class "Default")
      (node (ref "X2") (pin "3") (pinfunction "3_3") (pintype "passive"))
    )
  )
)
